# Main_EDA.net
KiCad netlist of a schematic drawn in Altium Designer
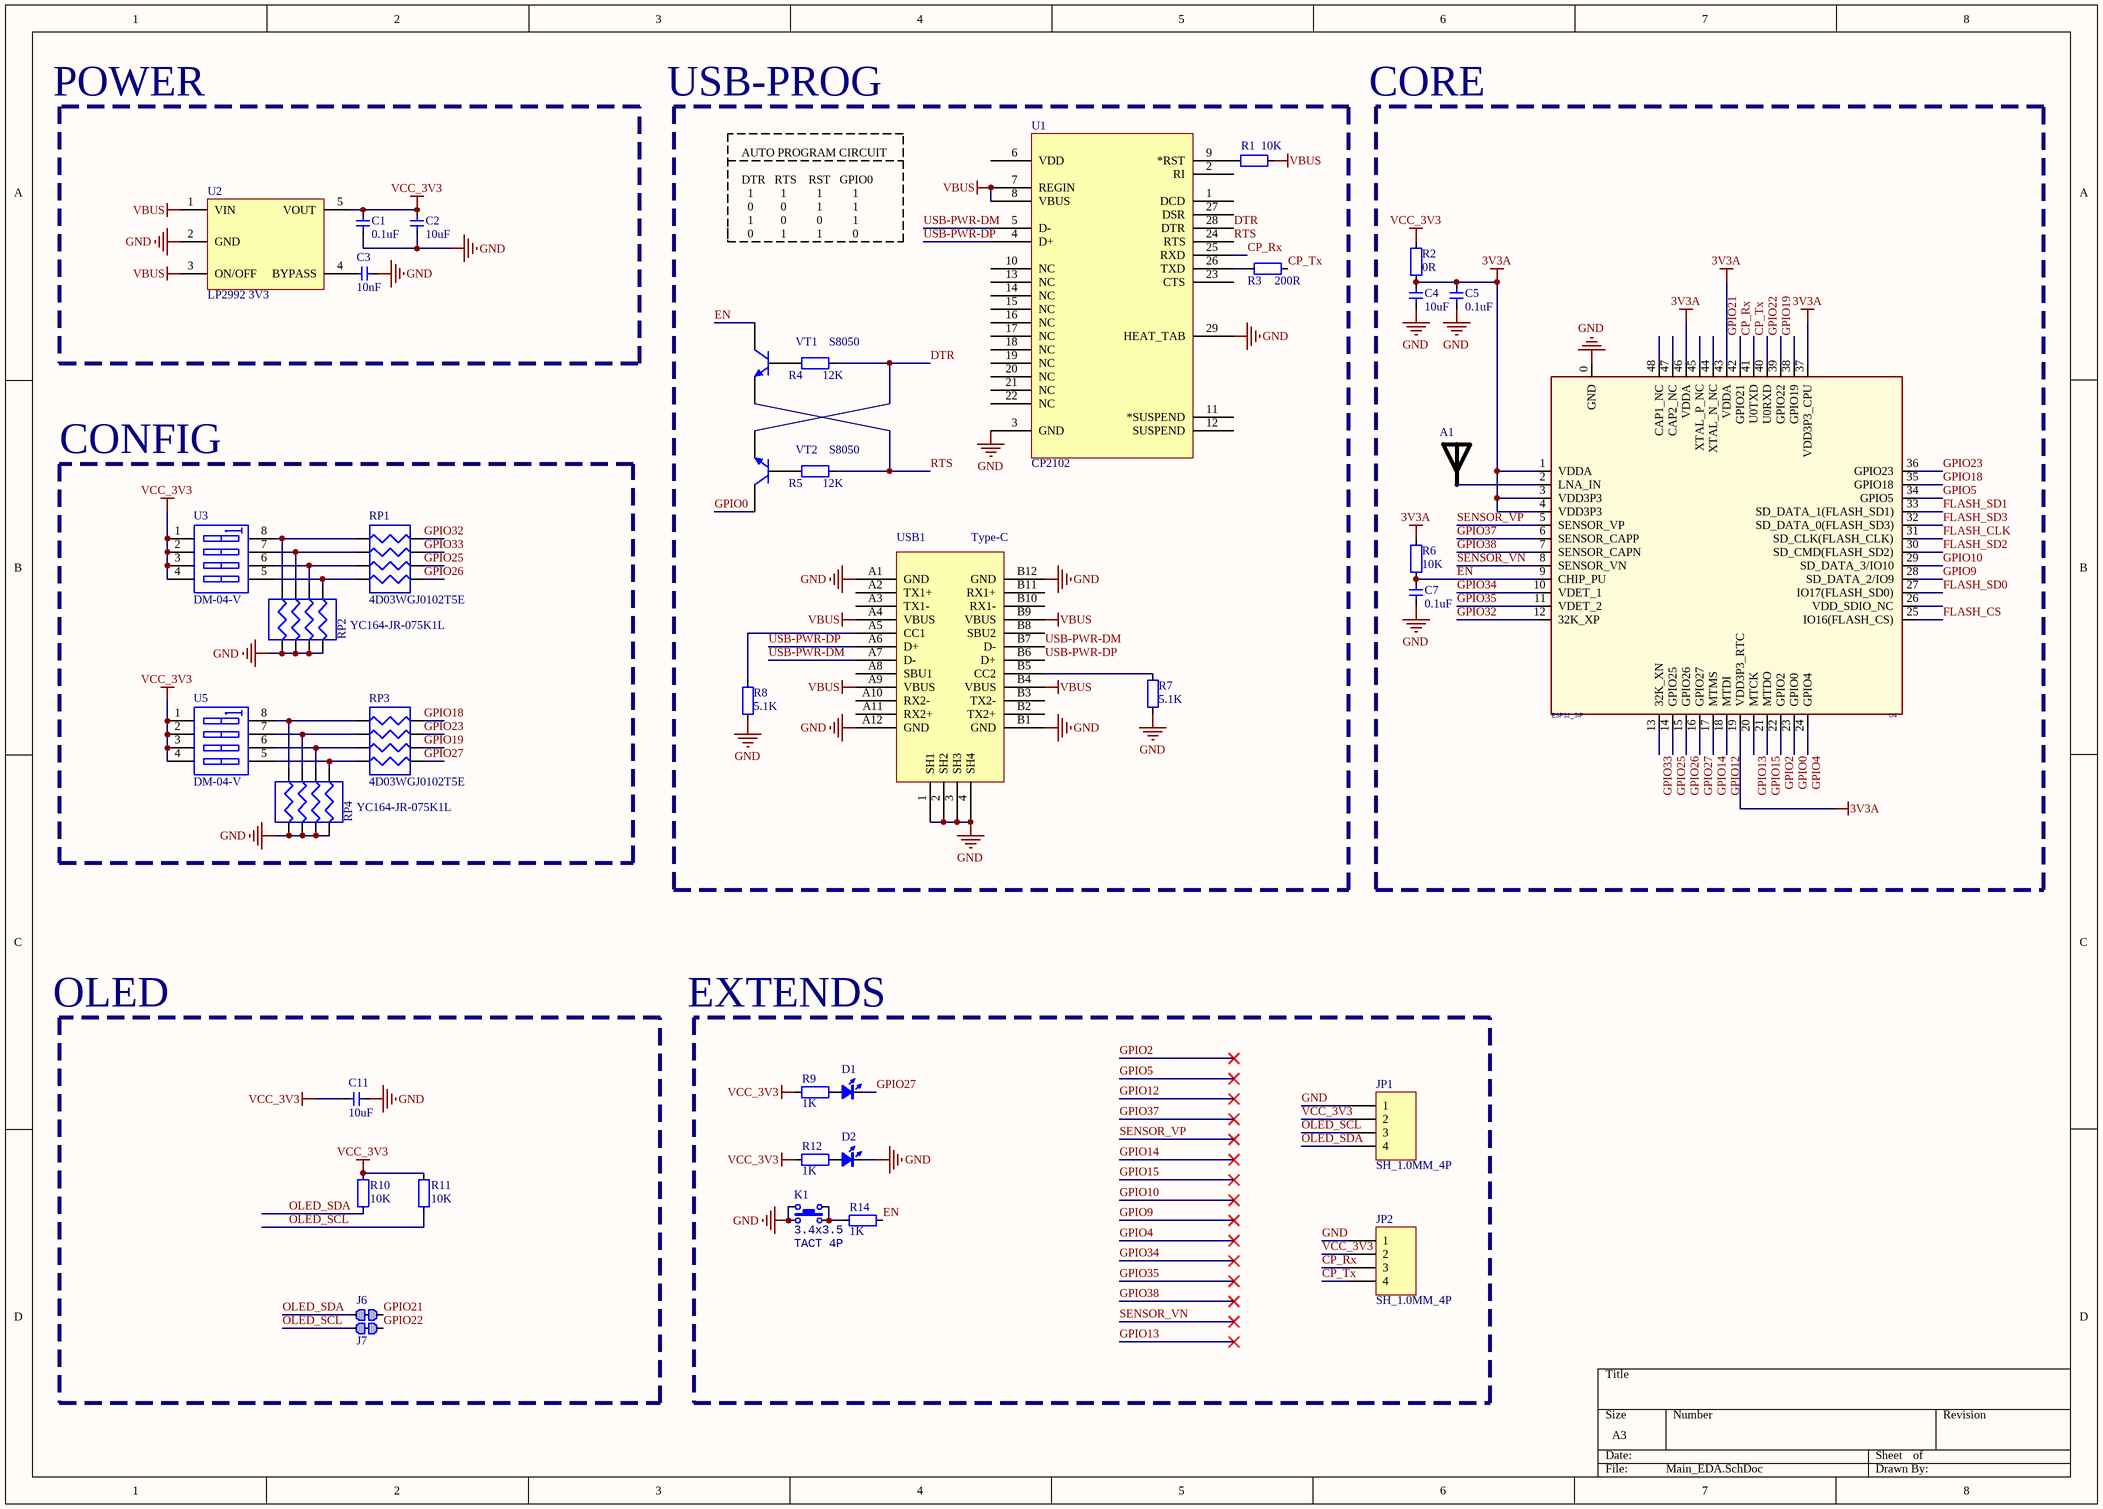
[diagram p0: Main_EDA.SchDoc]

(export (version "E")
  (design (tool "Eeschema 10.0.6"))
  (components
    (comp (ref "A1")
      (value "RAINSUN")
      (footprint "ANT-Rainsun-AN5120")
      (libsource (lib "MyPcbLib") (part "ANT-Rainsun-AP5120"))
    )
    (comp (ref "C1")
      (value "0.1uF")
      (footprint "CAP_0402")
      (description "Capacitor")
      (libsource (lib "MyPcbLib") (part "电容-0402"))
    )
    (comp (ref "C2")
      (value "10uF")
      (footprint "CAP_0402")
      (description "Capacitor")
      (libsource (lib "MyPcbLib") (part "电容-0402"))
    )
    (comp (ref "C3")
      (value "10nF")
      (footprint "CAP_0402")
      (description "Capacitor")
      (libsource (lib "MyPcbLib") (part "电容-0402"))
    )
    (comp (ref "C4")
      (value "10uF")
      (footprint "CAP_0402")
      (description "Capacitor")
      (libsource (lib "MyPcbLib") (part "电容-0402"))
    )
    (comp (ref "C5")
      (value "0.1uF")
      (footprint "CAP_0402")
      (description "Capacitor")
      (libsource (lib "MyPcbLib") (part "电容-0402"))
    )
    (comp (ref "C7")
      (value "0.1uF")
      (footprint "CAP_0402")
      (description "Capacitor")
      (libsource (lib "MyPcbLib") (part "电容-0402"))
    )
    (comp (ref "C11")
      (value "10uF")
      (footprint "CAP_0402")
      (description "Capacitor")
      (libsource (lib "MyPcbLib") (part "电容-0402"))
    )
    (comp (ref "D1")
      (value "color?")
      (footprint "LED_0402_RED")
      (description "LED")
      (libsource (lib "KitSprout") (part "LED_0402"))
    )
    (comp (ref "D2")
      (value "color?")
      (footprint "LED_0402_RED")
      (description "LED")
      (libsource (lib "KitSprout") (part "LED_0402"))
    )
    (comp (ref "J6")
      (value "跳线")
      (footprint "0402-0R")
      (description "Resistor")
      (fields (field (name "PUBLISHER") "Altium Limited"))
      (libsource (lib "MyPcbLib") (part "跳线"))
    )
    (comp (ref "J7")
      (value "跳线")
      (footprint "0402-0R")
      (description "Resistor")
      (fields (field (name "PUBLISHER") "Altium Limited"))
      (libsource (lib "MyPcbLib") (part "跳线"))
    )
    (comp (ref "JP1")
      (value "SH_1.0MM_4P")
      (footprint "HDR1X4")
      (fields (field (name "PUBLISHER") "Altium Limited"))
      (libsource (lib "foot") (part "SH_1.0MM_4P"))
    )
    (comp (ref "JP2")
      (value "SH_1.0MM_4P")
      (footprint "HDR1X4")
      (fields (field (name "PUBLISHER") "Altium Limited"))
      (libsource (lib "foot") (part "SH_1.0MM_4P"))
    )
    (comp (ref "K1")
      (value "3.4x3.5")
      (footprint "ButtonTACT_3.5*3.55_90")
      (description "Button")
      (fields (field (name "TYPE") "TACT 4P") (field (name "Comment") "TACT 4P"))
      (libsource (lib "KitSprout") (part "ButtonTACT"))
    )
    (comp (ref "R1")
      (value "10K")
      (footprint "RES_0402")
      (description "Resistor")
      (libsource (lib "") (part "电阻-0402_2"))
    )
    (comp (ref "R2")
      (value "0R")
      (footprint "RES_0402")
      (description "Resistor")
      (libsource (lib "") (part "电阻-0402_1"))
    )
    (comp (ref "R3")
      (value "200R")
      (footprint "RES_0402")
      (description "Resistor")
      (libsource (lib "") (part "电阻-0402_2"))
    )
    (comp (ref "R4")
      (value "12K")
      (footprint "RES_0402")
      (description "Resistor")
      (libsource (lib "") (part "电阻-0402_2"))
    )
    (comp (ref "R5")
      (value "12K")
      (footprint "RES_0402")
      (description "Resistor")
      (libsource (lib "") (part "电阻-0402_2"))
    )
    (comp (ref "R6")
      (value "10K")
      (footprint "RES_0402")
      (description "Resistor")
      (libsource (lib "") (part "电阻-0402_1"))
    )
    (comp (ref "R7")
      (value "5.1K")
      (footprint "RES_0402")
      (description "Resistor")
      (libsource (lib "") (part "电阻-0402_1"))
    )
    (comp (ref "R8")
      (value "5.1K")
      (footprint "RES_0402")
      (description "Resistor")
      (libsource (lib "") (part "电阻-0402_1"))
    )
    (comp (ref "R9")
      (value "1K")
      (footprint "RES_0402")
      (description "Resistor")
      (libsource (lib "MyPcbLib") (part "电阻-0402"))
    )
    (comp (ref "R10")
      (value "10K")
      (footprint "RES_0402")
      (description "Resistor")
      (libsource (lib "") (part "电阻-0402_3"))
    )
    (comp (ref "R11")
      (value "10K")
      (footprint "RES_0402")
      (description "Resistor")
      (libsource (lib "") (part "电阻-0402_3"))
    )
    (comp (ref "R12")
      (value "1K")
      (footprint "RES_0402")
      (description "Resistor")
      (libsource (lib "MyPcbLib") (part "电阻-0402"))
    )
    (comp (ref "R14")
      (value "1K")
      (footprint "RES_0402")
      (description "Resistor")
      (libsource (lib "MyPcbLib") (part "电阻-0402"))
    )
    (comp (ref "RP1")
      (value "4D03WGJ0102T5E")
      (footprint "RES-ARRAY-SMD_0603-8P-L3.2-W1.6-BL")
      (libsource (lib "Schlib1") (part "RP"))
    )
    (comp (ref "RP2")
      (value "YC164-JR-075K1L")
      (footprint "RES-ARRAY-SMD_0603-8P-L3.2-W1.6-BL")
      (libsource (lib "Schlib1") (part "RP"))
    )
    (comp (ref "RP3")
      (value "4D03WGJ0102T5E")
      (footprint "RES-ARRAY-SMD_0603-8P-L3.2-W1.6-BL")
      (libsource (lib "Schlib1") (part "RP"))
    )
    (comp (ref "RP4")
      (value "YC164-JR-075K1L")
      (footprint "RES-ARRAY-SMD_0603-8P-L3.2-W1.6-BL")
      (libsource (lib "Schlib1") (part "RP"))
    )
    (comp (ref "U1")
      (value "CP2102")
      (footprint "QFN-28")
      (description "USB转TTL")
      (libsource (lib "mLib") (part "CP2102"))
    )
    (comp (ref "U2")
      (value "LP2992 3V3")
      (footprint "SOT23-5")
      (description "LDO")
      (libsource (lib "MyPcbLib") (part "LP2992"))
    )
    (comp (ref "U3")
      (value "DM-04-V")
      (footprint "SW-SMD_8P-L11.1-W6.2-P2.54-LS9.8")
      (description "DIP Switch, 4 Position, SPST")
      (fields (field (name "PUBLISHER") "Altium Limited"))
      (libsource (lib "Miscellaneous Devices") (part "SW DIP-4"))
    )
    (comp (ref "U4")
      (value "ESP32_SIP")
      (footprint "QFN-48_7X7")
      (libsource (lib "MyPcbLib") (part "ESP32-PICO"))
    )
    (comp (ref "U5")
      (value "DM-04-V")
      (footprint "SW-SMD_8P-L11.1-W6.2-P2.54-LS9.8")
      (description "DIP Switch, 4 Position, SPST")
      (fields (field (name "PUBLISHER") "Altium Limited"))
      (libsource (lib "Miscellaneous Devices") (part "SW DIP-4"))
    )
    (comp (ref "USB1")
      (value "Type-C")
      (footprint "Type-C-TOP")
      (libsource (lib "MyPcbLib") (part "USB-Type-C-TOP"))
    )
    (comp (ref "VT1")
      (value "S8050")
      (footprint "SMT_TRIODE_NPN")
      (description "Surface mount NPN transistor, package SOT-23")
      (libsource (lib "MyPcbLib") (part "SMT_TRIODE_NPN"))
    )
    (comp (ref "VT2")
      (value "S8050")
      (footprint "SMT_TRIODE_NPN")
      (description "Surface mount NPN transistor, package SOT-23")
      (libsource (lib "MyPcbLib") (part "SMT_TRIODE_NPN"))
    )
  )
  (nets
    (net (code "1") (name "/CP_Rx") (class "Default")
      (node (ref "JP2") (pin "3") (pinfunction "3_3") (pintype "passive"))
      (node (ref "U1") (pin "25") (pinfunction "RXD_25") (pintype "passive"))
      (node (ref "U4") (pin "41") (pinfunction "U0TXD_41") (pintype "power_in"))
    )
    (net (code "2") (name "/CP_Tx") (class "Default")
      (node (ref "JP2") (pin "4") (pinfunction "4_4") (pintype "passive"))
      (node (ref "R3") (pin "1") (pinfunction "1_1") (pintype "passive"))
      (node (ref "U4") (pin "40") (pinfunction "U0RXD_40") (pintype "power_in"))
    )
    (net (code "3") (name "/DTR") (class "Default")
      (node (ref "R4") (pin "1") (pinfunction "1_1") (pintype "passive"))
      (node (ref "U1") (pin "28") (pinfunction "DTR_28") (pintype "passive"))
      (node (ref "VT2") (pin "2") (pinfunction "E_2") (pintype "passive"))
    )
    (net (code "4") (name "/EN") (class "Default")
      (node (ref "C7") (pin "1") (pinfunction "1_1") (pintype "passive"))
      (node (ref "R14") (pin "2") (pinfunction "2_2") (pintype "passive"))
      (node (ref "R6") (pin "2") (pinfunction "2_2") (pintype "passive"))
      (node (ref "U4") (pin "9") (pinfunction "CHIP_PU_9") (pintype "passive"))
      (node (ref "VT1") (pin "3") (pinfunction "C_3") (pintype "passive"))
    )
    (net (code "5") (name "/FLASH_CLK") (class "Default")
      (node (ref "U4") (pin "31") (pinfunction "SD_CLK(FLASH_CLK)_31") (pintype "passive"))
    )
    (net (code "6") (name "/FLASH_CS") (class "Default")
      (node (ref "U4") (pin "25") (pinfunction "IO16(FLASH_CS)_25") (pintype "passive"))
    )
    (net (code "7") (name "/FLASH_SD0") (class "Default")
      (node (ref "U4") (pin "27") (pinfunction "IO17(FLASH_SD0)_27") (pintype "passive"))
    )
    (net (code "8") (name "/FLASH_SD1") (class "Default")
      (node (ref "U4") (pin "33") (pinfunction "SD_DATA_1(FLASH_SD1)_33") (pintype "passive"))
    )
    (net (code "9") (name "/FLASH_SD2") (class "Default")
      (node (ref "U4") (pin "30") (pinfunction "SD_CMD(FLASH_SD2)_30") (pintype "passive"))
    )
    (net (code "10") (name "/FLASH_SD3") (class "Default")
      (node (ref "U4") (pin "32") (pinfunction "SD_DATA_0(FLASH_SD3)_32") (pintype "passive"))
    )
    (net (code "11") (name "/GPIO0") (class "Default")
      (node (ref "U4") (pin "23") (pinfunction "GPIO0_23") (pintype "passive"))
      (node (ref "VT2") (pin "3") (pinfunction "C_3") (pintype "passive"))
    )
    (net (code "12") (name "/GPIO2") (class "Default")
      (node (ref "U4") (pin "22") (pinfunction "GPIO2_22") (pintype "passive+no_connect"))
    )
    (net (code "13") (name "/GPIO4") (class "Default")
      (node (ref "U4") (pin "24") (pinfunction "GPIO4_24") (pintype "passive"))
    )
    (net (code "14") (name "/GPIO5") (class "Default")
      (node (ref "U4") (pin "34") (pinfunction "GPIO5_34") (pintype "passive"))
    )
    (net (code "15") (name "/GPIO9") (class "Default")
      (node (ref "U4") (pin "28") (pinfunction "SD_DATA_2/IO9_28") (pintype "passive"))
    )
    (net (code "16") (name "/GPIO10") (class "Default")
      (node (ref "U4") (pin "29") (pinfunction "SD_DATA_3/IO10_29") (pintype "passive"))
    )
    (net (code "17") (name "/GPIO12") (class "Default")
      (node (ref "U4") (pin "18") (pinfunction "MTDI_18") (pintype "passive+no_connect"))
    )
    (net (code "18") (name "/GPIO13") (class "Default")
      (node (ref "U4") (pin "20") (pinfunction "MTCK_20") (pintype "passive"))
    )
    (net (code "19") (name "/GPIO14") (class "Default")
      (node (ref "U4") (pin "17") (pinfunction "MTMS_17") (pintype "passive"))
    )
    (net (code "20") (name "/GPIO15") (class "Default")
      (node (ref "U4") (pin "21") (pinfunction "MTDO_21") (pintype "passive"))
    )
    (net (code "21") (name "/GPIO18") (class "Default")
      (node (ref "RP3") (pin "8") (pinfunction "8_8") (pintype "passive"))
      (node (ref "U4") (pin "35") (pinfunction "GPIO18_35") (pintype "passive"))
    )
    (net (code "22") (name "/GPIO19") (class "Default")
      (node (ref "RP3") (pin "6") (pinfunction "6_6") (pintype "passive"))
      (node (ref "U4") (pin "38") (pinfunction "GPIO19_38") (pintype "passive"))
    )
    (net (code "23") (name "/GPIO21") (class "Default")
      (node (ref "J6") (pin "2") (pinfunction "2_2") (pintype "passive"))
      (node (ref "U4") (pin "42") (pinfunction "GPIO21_42") (pintype "passive"))
    )
    (net (code "24") (name "/GPIO22") (class "Default")
      (node (ref "J7") (pin "2") (pinfunction "2_2") (pintype "passive"))
      (node (ref "U4") (pin "39") (pinfunction "GPIO22_39") (pintype "passive"))
    )
    (net (code "25") (name "/GPIO23") (class "Default")
      (node (ref "RP3") (pin "7") (pinfunction "7_7") (pintype "passive"))
      (node (ref "U4") (pin "36") (pinfunction "GPIO23_36") (pintype "passive"))
    )
    (net (code "26") (name "/GPIO25") (class "Default")
      (node (ref "RP1") (pin "6") (pinfunction "6_6") (pintype "passive"))
      (node (ref "U4") (pin "14") (pinfunction "GPIO25_14") (pintype "passive"))
    )
    (net (code "27") (name "/GPIO26") (class "Default")
      (node (ref "RP1") (pin "5") (pinfunction "5_5") (pintype "passive"))
      (node (ref "U4") (pin "15") (pinfunction "GPIO26_15") (pintype "passive"))
    )
    (net (code "28") (name "/GPIO27") (class "Default")
      (node (ref "D1") (pin "2") (pinfunction "K_2") (pintype "passive"))
      (node (ref "RP3") (pin "5") (pinfunction "5_5") (pintype "passive"))
      (node (ref "U4") (pin "16") (pinfunction "GPIO27_16") (pintype "passive"))
    )
    (net (code "29") (name "/GPIO32") (class "Default")
      (node (ref "RP1") (pin "8") (pinfunction "8_8") (pintype "passive"))
      (node (ref "U4") (pin "12") (pinfunction "32K_XP_12") (pintype "passive"))
    )
    (net (code "30") (name "/GPIO33") (class "Default")
      (node (ref "RP1") (pin "7") (pinfunction "7_7") (pintype "passive"))
      (node (ref "U4") (pin "13") (pinfunction "32K_XN_13") (pintype "passive"))
    )
    (net (code "31") (name "/GPIO34") (class "Default")
      (node (ref "U4") (pin "10") (pinfunction "VDET_1_10") (pintype "passive"))
    )
    (net (code "32") (name "/GPIO35") (class "Default")
      (node (ref "U4") (pin "11") (pinfunction "VDET_2_11") (pintype "passive"))
    )
    (net (code "33") (name "/GPIO37") (class "Default")
      (node (ref "U4") (pin "6") (pinfunction "SENSOR_CAPP_6") (pintype "passive"))
    )
    (net (code "34") (name "/GPIO38") (class "Default")
      (node (ref "U4") (pin "7") (pinfunction "SENSOR_CAPN_7") (pintype "passive"))
    )
    (net (code "35") (name "/OLED_SCL") (class "Default")
      (node (ref "J7") (pin "1") (pinfunction "1_1") (pintype "passive"))
      (node (ref "JP1") (pin "3") (pinfunction "3_3") (pintype "passive"))
      (node (ref "R11") (pin "1") (pinfunction "1_1") (pintype "passive"))
    )
    (net (code "36") (name "/OLED_SDA") (class "Default")
      (node (ref "J6") (pin "1") (pinfunction "1_1") (pintype "passive"))
      (node (ref "JP1") (pin "4") (pinfunction "4_4") (pintype "passive"))
      (node (ref "R10") (pin "1") (pinfunction "1_1") (pintype "passive"))
    )
    (net (code "37") (name "/RTS") (class "Default")
      (node (ref "R5") (pin "1") (pinfunction "1_1") (pintype "passive"))
      (node (ref "U1") (pin "24") (pinfunction "RTS_24") (pintype "passive"))
      (node (ref "VT1") (pin "2") (pinfunction "E_2") (pintype "passive"))
    )
    (net (code "38") (name "/SENSOR_VN") (class "Default")
      (node (ref "U4") (pin "8") (pinfunction "SENSOR_VN_8") (pintype "passive"))
    )
    (net (code "39") (name "/SENSOR_VP") (class "Default")
      (node (ref "U4") (pin "5") (pinfunction "SENSOR_VP_5") (pintype "passive"))
    )
    (net (code "40") (name "/USB-PWR-DM") (class "Default")
      (node (ref "U1") (pin "5") (pinfunction "D-_5") (pintype "passive"))
      (node (ref "USB1") (pin "A7") (pinfunction "D-_A7") (pintype "passive"))
      (node (ref "USB1") (pin "B7") (pinfunction "D-_B7") (pintype "passive"))
    )
    (net (code "41") (name "/USB-PWR-DP") (class "Default")
      (node (ref "U1") (pin "4") (pinfunction "D+_4") (pintype "passive"))
      (node (ref "USB1") (pin "A6") (pinfunction "D+_A6") (pintype "passive"))
      (node (ref "USB1") (pin "B6") (pinfunction "D+_B6") (pintype "passive"))
    )
    (net (code "42") (name "3V3A") (class "Default")
      (node (ref "C4") (pin "2") (pinfunction "2_2") (pintype "passive"))
      (node (ref "C5") (pin "2") (pinfunction "2_2") (pintype "passive"))
      (node (ref "R2") (pin "2") (pinfunction "2_2") (pintype "passive"))
      (node (ref "R6") (pin "1") (pinfunction "1_1") (pintype "passive"))
      (node (ref "U4") (pin "1") (pinfunction "VDDA_1") (pintype "power_in"))
      (node (ref "U4") (pin "19") (pinfunction "VDD3P3_RTC_19") (pintype "power_in"))
      (node (ref "U4") (pin "3") (pinfunction "VDD3P3_3") (pintype "power_in"))
      (node (ref "U4") (pin "37") (pinfunction "VDD3P3_CPU_37") (pintype "power_in"))
      (node (ref "U4") (pin "4") (pinfunction "VDD3P3_4") (pintype "power_in"))
      (node (ref "U4") (pin "43") (pinfunction "VDDA_43") (pintype "power_in"))
      (node (ref "U4") (pin "46") (pinfunction "VDDA_46") (pintype "power_in"))
    )
    (net (code "43") (name "GND") (class "Default")
      (node (ref "C1") (pin "1") (pinfunction "1_1") (pintype "passive"))
      (node (ref "C11") (pin "1") (pinfunction "1_1") (pintype "passive"))
      (node (ref "C2") (pin "1") (pinfunction "1_1") (pintype "passive"))
      (node (ref "C3") (pin "1") (pinfunction "1_1") (pintype "passive"))
      (node (ref "C4") (pin "1") (pinfunction "1_1") (pintype "passive"))
      (node (ref "C5") (pin "1") (pinfunction "1_1") (pintype "passive"))
      (node (ref "C7") (pin "2") (pinfunction "2_2") (pintype "passive"))
      (node (ref "D2") (pin "2") (pinfunction "K_2") (pintype "passive"))
      (node (ref "JP1") (pin "1") (pinfunction "1_1") (pintype "passive"))
      (node (ref "JP2") (pin "1") (pinfunction "1_1") (pintype "passive"))
      (node (ref "K1") (pin "1") (pinfunction "1_1") (pintype "passive"))
      (node (ref "K1") (pin "3") (pinfunction "3_3") (pintype "passive"))
      (node (ref "R7") (pin "2") (pinfunction "2_2") (pintype "passive"))
      (node (ref "R8") (pin "2") (pinfunction "2_2") (pintype "passive"))
      (node (ref "RP2") (pin "5") (pinfunction "5_5") (pintype "passive"))
      (node (ref "RP2") (pin "6") (pinfunction "6_6") (pintype "passive"))
      (node (ref "RP2") (pin "7") (pinfunction "7_7") (pintype "passive"))
      (node (ref "RP2") (pin "8") (pinfunction "8_8") (pintype "passive"))
      (node (ref "RP4") (pin "5") (pinfunction "5_5") (pintype "passive"))
      (node (ref "RP4") (pin "6") (pinfunction "6_6") (pintype "passive"))
      (node (ref "RP4") (pin "7") (pinfunction "7_7") (pintype "passive"))
      (node (ref "RP4") (pin "8") (pinfunction "8_8") (pintype "passive"))
      (node (ref "U1") (pin "29") (pinfunction "HEAT_TAB_29") (pintype "passive"))
      (node (ref "U1") (pin "3") (pinfunction "GND_3") (pintype "passive"))
      (node (ref "U2") (pin "2") (pinfunction "GND_2") (pintype "passive"))
      (node (ref "U4") (pin "0") (pinfunction "GND_0") (pintype "power_in"))
      (node (ref "USB1") (pin "1") (pinfunction "SH1_1") (pintype "passive"))
      (node (ref "USB1") (pin "2") (pinfunction "SH2_2") (pintype "passive"))
      (node (ref "USB1") (pin "3") (pinfunction "SH3_3") (pintype "passive"))
      (node (ref "USB1") (pin "4") (pinfunction "SH4_4") (pintype "passive"))
      (node (ref "USB1") (pin "A1") (pinfunction "GND_A1") (pintype "passive"))
      (node (ref "USB1") (pin "A12") (pinfunction "GND_A12") (pintype "passive"))
      (node (ref "USB1") (pin "B1") (pinfunction "GND_B1") (pintype "passive"))
      (node (ref "USB1") (pin "B12") (pinfunction "GND_B12") (pintype "passive"))
    )
    (net (code "44") (name "Net-(D1-A)") (class "Default")
      (node (ref "D1") (pin "1") (pinfunction "A_1") (pintype "passive"))
      (node (ref "R9") (pin "2") (pinfunction "2_2") (pintype "passive"))
    )
    (net (code "45") (name "Net-(D2-A)") (class "Default")
      (node (ref "D2") (pin "1") (pinfunction "A_1") (pintype "passive"))
      (node (ref "R12") (pin "2") (pinfunction "2_2") (pintype "passive"))
    )
    (net (code "46") (name "Net-(K1-Pad2)") (class "Default")
      (node (ref "K1") (pin "2") (pinfunction "2_2") (pintype "passive"))
      (node (ref "K1") (pin "4") (pinfunction "4_4") (pintype "passive"))
      (node (ref "R14") (pin "1") (pinfunction "1_1") (pintype "passive"))
    )
    (net (code "47") (name "Net-(U1-*RST)") (class "Default")
      (node (ref "R1") (pin "2") (pinfunction "2_2") (pintype "passive"))
      (node (ref "U1") (pin "9") (pinfunction "*RST_9") (pintype "passive"))
    )
    (net (code "48") (name "Net-(U1-TXD)") (class "Default")
      (node (ref "R3") (pin "2") (pinfunction "2_2") (pintype "passive"))
      (node (ref "U1") (pin "26") (pinfunction "TXD_26") (pintype "passive"))
    )
    (net (code "49") (name "Net-(U2-BYPASS)") (class "Default")
      (node (ref "C3") (pin "2") (pinfunction "2_2") (pintype "passive"))
      (node (ref "U2") (pin "4") (pinfunction "BYPASS_4") (pintype "passive"))
    )
    (net (code "50") (name "Net-(U3-B1)") (class "Default")
      (node (ref "RP1") (pin "1") (pinfunction "1_1") (pintype "passive"))
      (node (ref "RP2") (pin "4") (pinfunction "4_4") (pintype "passive"))
      (node (ref "U3") (pin "8") (pinfunction "B1_8") (pintype "passive"))
    )
    (net (code "51") (name "Net-(U3-B2)") (class "Default")
      (node (ref "RP1") (pin "2") (pinfunction "2_2") (pintype "passive"))
      (node (ref "RP2") (pin "3") (pinfunction "3_3") (pintype "passive"))
      (node (ref "U3") (pin "7") (pinfunction "B2_7") (pintype "passive"))
    )
    (net (code "52") (name "Net-(U3-B3)") (class "Default")
      (node (ref "RP1") (pin "3") (pinfunction "3_3") (pintype "passive"))
      (node (ref "RP2") (pin "2") (pinfunction "2_2") (pintype "passive"))
      (node (ref "U3") (pin "6") (pinfunction "B3_6") (pintype "passive"))
    )
    (net (code "53") (name "Net-(U3-B4)") (class "Default")
      (node (ref "RP1") (pin "4") (pinfunction "4_4") (pintype "passive"))
      (node (ref "RP2") (pin "1") (pinfunction "1_1") (pintype "passive"))
      (node (ref "U3") (pin "5") (pinfunction "B4_5") (pintype "passive"))
    )
    (net (code "54") (name "Net-(U4-LNA_IN)") (class "Default")
      (node (ref "A1") (pin "1") (pinfunction "1_1") (pintype "passive"))
      (node (ref "U4") (pin "2") (pinfunction "LNA_IN_2") (pintype "passive"))
    )
    (net (code "55") (name "Net-(U5-B1)") (class "Default")
      (node (ref "RP3") (pin "1") (pinfunction "1_1") (pintype "passive"))
      (node (ref "RP4") (pin "4") (pinfunction "4_4") (pintype "passive"))
      (node (ref "U5") (pin "8") (pinfunction "B1_8") (pintype "passive"))
    )
    (net (code "56") (name "Net-(U5-B2)") (class "Default")
      (node (ref "RP3") (pin "2") (pinfunction "2_2") (pintype "passive"))
      (node (ref "RP4") (pin "3") (pinfunction "3_3") (pintype "passive"))
      (node (ref "U5") (pin "7") (pinfunction "B2_7") (pintype "passive"))
    )
    (net (code "57") (name "Net-(U5-B3)") (class "Default")
      (node (ref "RP3") (pin "3") (pinfunction "3_3") (pintype "passive"))
      (node (ref "RP4") (pin "2") (pinfunction "2_2") (pintype "passive"))
      (node (ref "U5") (pin "6") (pinfunction "B3_6") (pintype "passive"))
    )
    (net (code "58") (name "Net-(U5-B4)") (class "Default")
      (node (ref "RP3") (pin "4") (pinfunction "4_4") (pintype "passive"))
      (node (ref "RP4") (pin "1") (pinfunction "1_1") (pintype "passive"))
      (node (ref "U5") (pin "5") (pinfunction "B4_5") (pintype "passive"))
    )
    (net (code "59") (name "Net-(USB1-CC1)") (class "Default")
      (node (ref "R8") (pin "1") (pinfunction "1_1") (pintype "passive"))
      (node (ref "USB1") (pin "A5") (pinfunction "CC1_A5") (pintype "passive"))
    )
    (net (code "60") (name "Net-(USB1-CC2)") (class "Default")
      (node (ref "R7") (pin "1") (pinfunction "1_1") (pintype "passive"))
      (node (ref "USB1") (pin "B5") (pinfunction "CC2_B5") (pintype "passive"))
    )
    (net (code "61") (name "Net-(VT1-B)") (class "Default")
      (node (ref "R4") (pin "2") (pinfunction "2_2") (pintype "passive"))
      (node (ref "VT1") (pin "1") (pinfunction "B_1") (pintype "passive"))
    )
    (net (code "62") (name "Net-(VT2-B)") (class "Default")
      (node (ref "R5") (pin "2") (pinfunction "2_2") (pintype "passive"))
      (node (ref "VT2") (pin "1") (pinfunction "B_1") (pintype "passive"))
    )
    (net (code "63") (name "VBUS") (class "Default")
      (node (ref "R1") (pin "1") (pinfunction "1_1") (pintype "passive"))
      (node (ref "U1") (pin "7") (pinfunction "REGIN_7") (pintype "passive"))
      (node (ref "U1") (pin "8") (pinfunction "VBUS_8") (pintype "passive"))
      (node (ref "U2") (pin "1") (pinfunction "VIN_1") (pintype "passive"))
      (node (ref "U2") (pin "3") (pinfunction "ON/OFF_3") (pintype "passive"))
      (node (ref "USB1") (pin "A4") (pinfunction "VBUS_A4") (pintype "passive"))
      (node (ref "USB1") (pin "A9") (pinfunction "VBUS_A9") (pintype "passive"))
      (node (ref "USB1") (pin "B4") (pinfunction "VBUS_B4") (pintype "passive"))
      (node (ref "USB1") (pin "B9") (pinfunction "VBUS_B9") (pintype "passive"))
    )
    (net (code "64") (name "VCC_3V3") (class "Default")
      (node (ref "C1") (pin "2") (pinfunction "2_2") (pintype "passive"))
      (node (ref "C11") (pin "2") (pinfunction "2_2") (pintype "passive"))
      (node (ref "C2") (pin "2") (pinfunction "2_2") (pintype "passive"))
      (node (ref "JP1") (pin "2") (pinfunction "2_2") (pintype "passive"))
      (node (ref "JP2") (pin "2") (pinfunction "2_2") (pintype "passive"))
      (node (ref "R10") (pin "2") (pinfunction "2_2") (pintype "passive"))
      (node (ref "R11") (pin "2") (pinfunction "2_2") (pintype "passive"))
      (node (ref "R12") (pin "1") (pinfunction "1_1") (pintype "passive"))
      (node (ref "R2") (pin "1") (pinfunction "1_1") (pintype "passive"))
      (node (ref "R9") (pin "1") (pinfunction "1_1") (pintype "passive"))
      (node (ref "U2") (pin "5") (pinfunction "VOUT_5") (pintype "passive"))
      (node (ref "U3") (pin "1") (pinfunction "A1_1") (pintype "passive"))
      (node (ref "U3") (pin "2") (pinfunction "A2_2") (pintype "passive"))
      (node (ref "U3") (pin "3") (pinfunction "A3_3") (pintype "passive"))
      (node (ref "U3") (pin "4") (pinfunction "A4_4") (pintype "passive"))
      (node (ref "U5") (pin "1") (pinfunction "A1_1") (pintype "passive"))
      (node (ref "U5") (pin "2") (pinfunction "A2_2") (pintype "passive"))
      (node (ref "U5") (pin "3") (pinfunction "A3_3") (pintype "passive"))
      (node (ref "U5") (pin "4") (pinfunction "A4_4") (pintype "passive"))
    )
    (net (code "65") (name "unconnected-(U1-*SUSPEND-Pad11)") (class "Default")
      (node (ref "U1") (pin "11") (pinfunction "*SUSPEND_11") (pintype "passive"))
    )
    (net (code "66") (name "unconnected-(U1-CTS-Pad23)") (class "Default")
      (node (ref "U1") (pin "23") (pinfunction "CTS_23") (pintype "passive"))
    )
    (net (code "67") (name "unconnected-(U1-DCD-Pad1)") (class "Default")
      (node (ref "U1") (pin "1") (pinfunction "DCD_1") (pintype "passive"))
    )
    (net (code "68") (name "unconnected-(U1-DSR-Pad27)") (class "Default")
      (node (ref "U1") (pin "27") (pinfunction "DSR_27") (pintype "passive"))
    )
    (net (code "69") (name "unconnected-(U1-NC-Pad10)") (class "Default")
      (node (ref "U1") (pin "10") (pinfunction "NC_10") (pintype "passive"))
    )
    (net (code "70") (name "unconnected-(U1-NC-Pad13)") (class "Default")
      (node (ref "U1") (pin "13") (pinfunction "NC_13") (pintype "passive"))
    )
    (net (code "71") (name "unconnected-(U1-NC-Pad14)") (class "Default")
      (node (ref "U1") (pin "14") (pinfunction "NC_14") (pintype "passive"))
    )
    (net (code "72") (name "unconnected-(U1-NC-Pad15)") (class "Default")
      (node (ref "U1") (pin "15") (pinfunction "NC_15") (pintype "passive"))
    )
    (net (code "73") (name "unconnected-(U1-NC-Pad16)") (class "Default")
      (node (ref "U1") (pin "16") (pinfunction "NC_16") (pintype "passive"))
    )
    (net (code "74") (name "unconnected-(U1-NC-Pad17)") (class "Default")
      (node (ref "U1") (pin "17") (pinfunction "NC_17") (pintype "passive"))
    )
    (net (code "75") (name "unconnected-(U1-NC-Pad18)") (class "Default")
      (node (ref "U1") (pin "18") (pinfunction "NC_18") (pintype "passive"))
    )
    (net (code "76") (name "unconnected-(U1-NC-Pad19)") (class "Default")
      (node (ref "U1") (pin "19") (pinfunction "NC_19") (pintype "passive"))
    )
    (net (code "77") (name "unconnected-(U1-NC-Pad20)") (class "Default")
      (node (ref "U1") (pin "20") (pinfunction "NC_20") (pintype "passive"))
    )
    (net (code "78") (name "unconnected-(U1-NC-Pad21)") (class "Default")
      (node (ref "U1") (pin "21") (pinfunction "NC_21") (pintype "passive"))
    )
    (net (code "79") (name "unconnected-(U1-NC-Pad22)") (class "Default")
      (node (ref "U1") (pin "22") (pinfunction "NC_22") (pintype "passive"))
    )
    (net (code "80") (name "unconnected-(U1-RI-Pad2)") (class "Default")
      (node (ref "U1") (pin "2") (pinfunction "RI_2") (pintype "passive"))
    )
    (net (code "81") (name "unconnected-(U1-SUSPEND-Pad12)") (class "Default")
      (node (ref "U1") (pin "12") (pinfunction "SUSPEND_12") (pintype "passive"))
    )
    (net (code "82") (name "unconnected-(U1-VDD-Pad6)") (class "Default")
      (node (ref "U1") (pin "6") (pinfunction "VDD_6") (pintype "passive"))
    )
    (net (code "83") (name "unconnected-(U4-CAP1_NC-Pad48)") (class "Default")
      (node (ref "U4") (pin "48") (pinfunction "CAP1_NC_48") (pintype "passive"))
    )
    (net (code "84") (name "unconnected-(U4-CAP2_NC-Pad47)") (class "Default")
      (node (ref "U4") (pin "47") (pinfunction "CAP2_NC_47") (pintype "passive"))
    )
    (net (code "85") (name "unconnected-(U4-VDD_SDIO_NC-Pad26)") (class "Default")
      (node (ref "U4") (pin "26") (pinfunction "VDD_SDIO_NC_26") (pintype "passive"))
    )
    (net (code "86") (name "unconnected-(U4-XTAL_N_NC-Pad44)") (class "Default")
      (node (ref "U4") (pin "44") (pinfunction "XTAL_N_NC_44") (pintype "passive"))
    )
    (net (code "87") (name "unconnected-(U4-XTAL_P_NC-Pad45)") (class "Default")
      (node (ref "U4") (pin "45") (pinfunction "XTAL_P_NC_45") (pintype "passive"))
    )
    (net (code "88") (name "unconnected-(USB1-RX1+-PadB11)") (class "Default")
      (node (ref "USB1") (pin "B11") (pinfunction "RX1+_B11") (pintype "passive"))
    )
    (net (code "89") (name "unconnected-(USB1-RX1--PadB10)") (class "Default")
      (node (ref "USB1") (pin "B10") (pinfunction "RX1-_B10") (pintype "passive"))
    )
    (net (code "90") (name "unconnected-(USB1-RX2+-PadA11)") (class "Default")
      (node (ref "USB1") (pin "A11") (pinfunction "RX2+_A11") (pintype "passive"))
    )
    (net (code "91") (name "unconnected-(USB1-RX2--PadA10)") (class "Default")
      (node (ref "USB1") (pin "A10") (pinfunction "RX2-_A10") (pintype "passive"))
    )
    (net (code "92") (name "unconnected-(USB1-SBU1-PadA8)") (class "Default")
      (node (ref "USB1") (pin "A8") (pinfunction "SBU1_A8") (pintype "passive"))
    )
    (net (code "93") (name "unconnected-(USB1-SBU2-PadB8)") (class "Default")
      (node (ref "USB1") (pin "B8") (pinfunction "SBU2_B8") (pintype "passive"))
    )
    (net (code "94") (name "unconnected-(USB1-TX1+-PadA2)") (class "Default")
      (node (ref "USB1") (pin "A2") (pinfunction "TX1+_A2") (pintype "passive"))
    )
    (net (code "95") (name "unconnected-(USB1-TX1--PadA3)") (class "Default")
      (node (ref "USB1") (pin "A3") (pinfunction "TX1-_A3") (pintype "passive"))
    )
    (net (code "96") (name "unconnected-(USB1-TX2+-PadB2)") (class "Default")
      (node (ref "USB1") (pin "B2") (pinfunction "TX2+_B2") (pintype "passive"))
    )
    (net (code "97") (name "unconnected-(USB1-TX2--PadB3)") (class "Default")
      (node (ref "USB1") (pin "B3") (pinfunction "TX2-_B3") (pintype "passive"))
    )
  )
)
